# Xenium2019.net
KiCad netlist of a schematic drawn in EAGLE
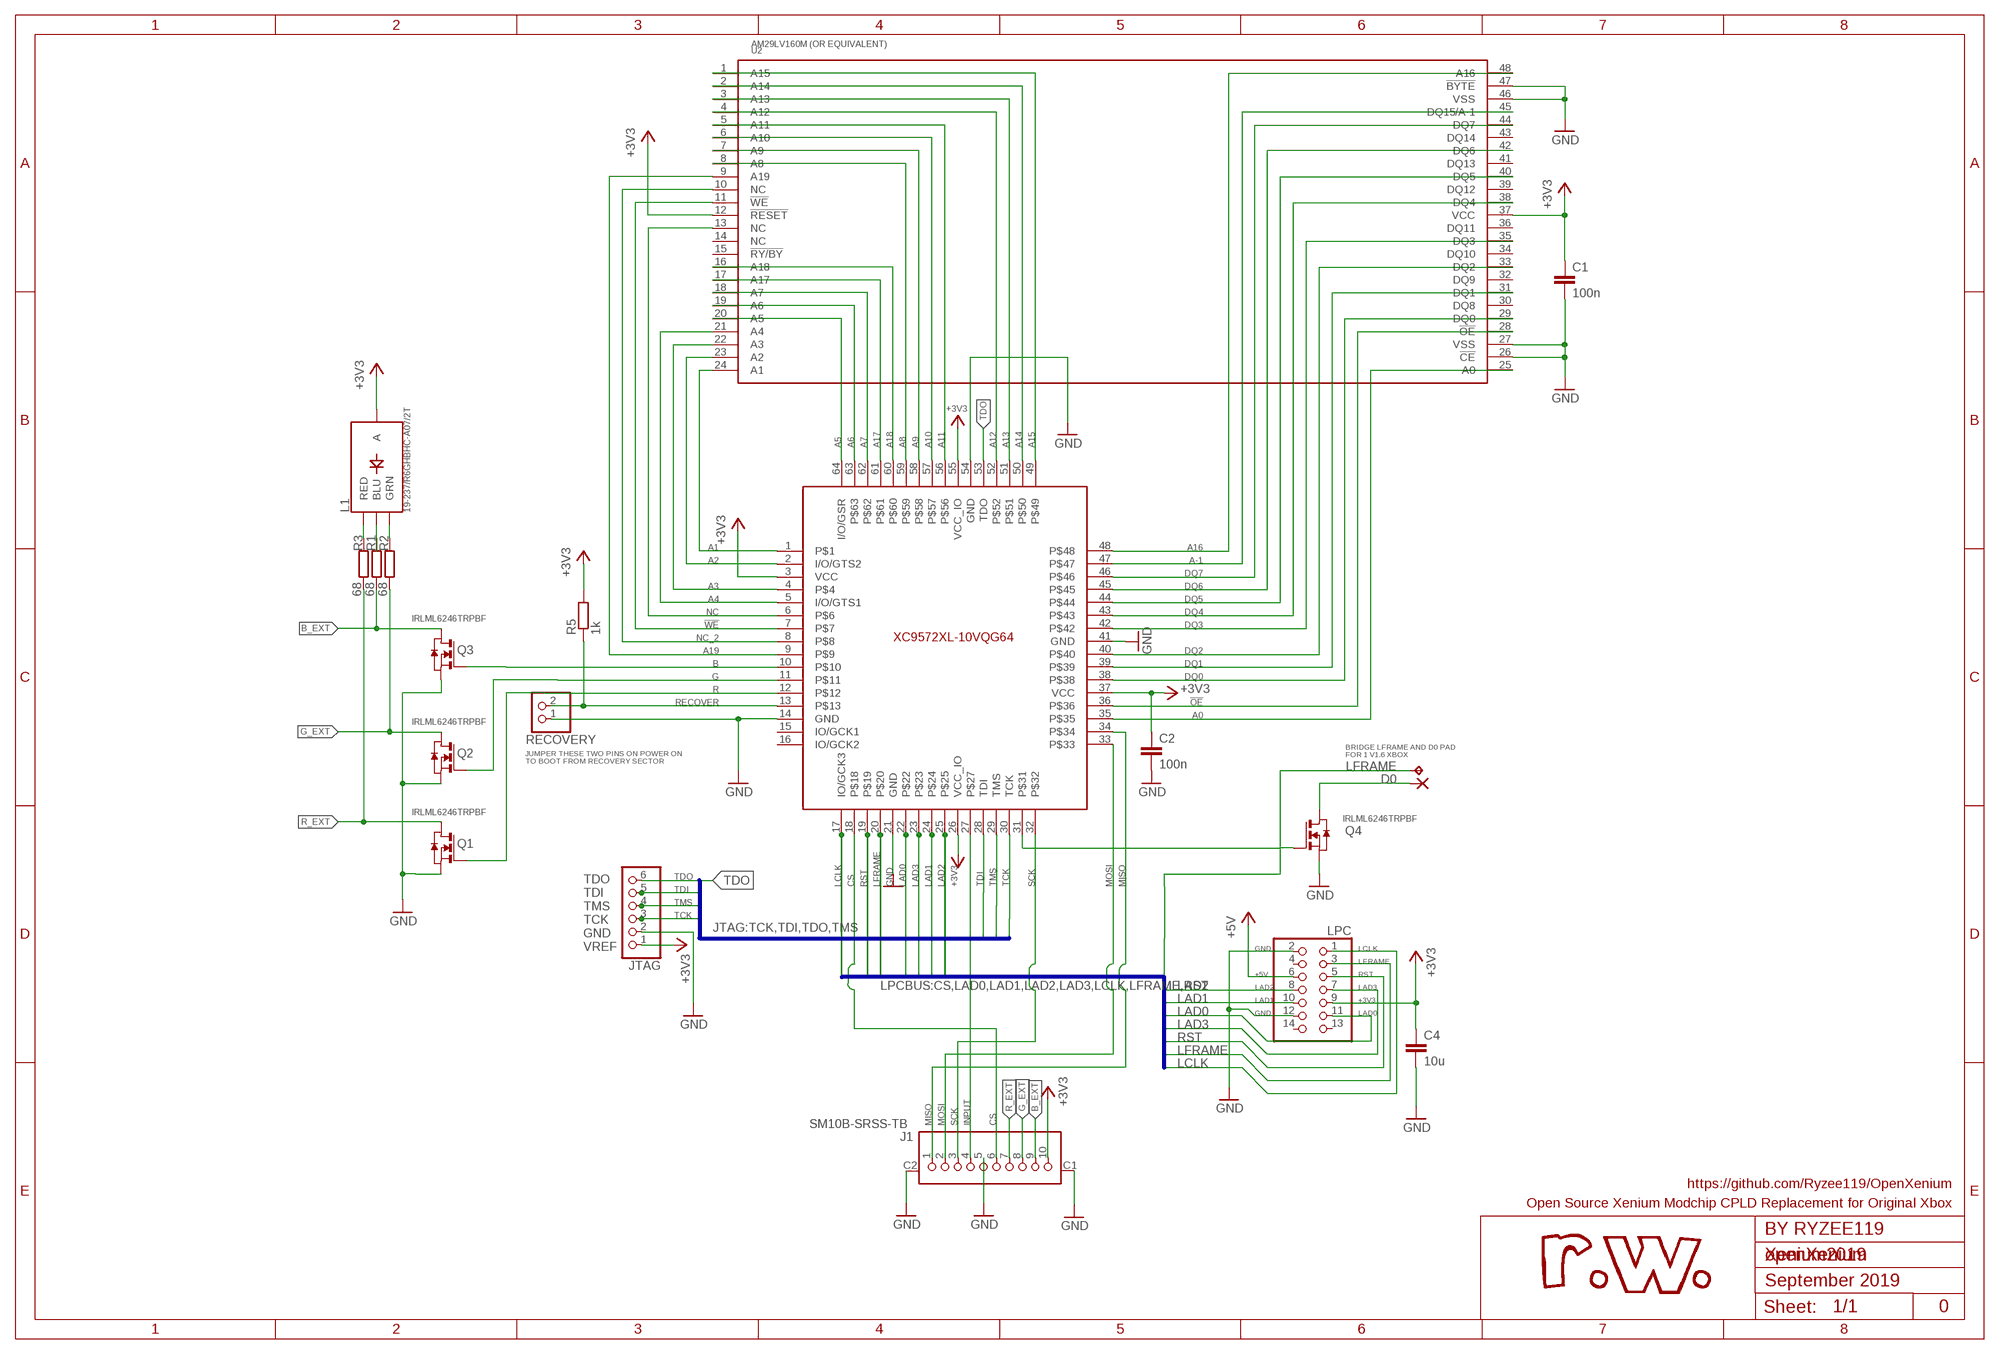
[diagram p0: schematic, sheet 1]

(export (version "E")
  (design (tool "Eeschema 10.0.6"))
  (components
    (comp (ref "C1")
      (value "100n")
      (footprint "eagle-import:C0603")
      (libsource (lib "eagle-import") (part "C-EUC0603"))
    )
    (comp (ref "C2")
      (value "100n")
      (footprint "eagle-import:C0603")
      (libsource (lib "eagle-import") (part "C-EUC0603"))
    )
    (comp (ref "C4")
      (value "10u")
      (footprint "eagle-import:C0603")
      (libsource (lib "eagle-import") (part "C-EUC0603"))
    )
    (comp (ref "D0")
      (value "SMD2")
      (footprint "eagle-import:SMD1,27-2,54")
      (libsource (lib "eagle-import") (part "SMD2"))
    )
    (comp (ref "J1")
      (value "SM10B-SRSS-TB")
      (footprint "eagle-import:SM10B-SRSS-TB")
      (libsource (lib "eagle-import") (part "SM10B-SRSS-TB"))
    )
    (comp (ref "JTAG")
      (value "PINHD-1X6")
      (footprint "eagle-import:1X06")
      (libsource (lib "eagle-import") (part "PINHD-1X6"))
    )
    (comp (ref "L1")
      (value "19-237/R6GHBHC-A07/2T")
      (footprint "eagle-import:4-SMD-R6GHBHC")
      (libsource (lib "eagle-import") (part "19-237/R6GHBHC-A07/2T"))
    )
    (comp (ref "LPC")
      (value "PINHD-2X7")
      (footprint "eagle-import:2X07")
      (libsource (lib "eagle-import") (part "PINHD-2X7"))
    )
    (comp (ref "Q1")
      (value "310mA/60V/1.6Ω")
      (footprint "eagle-import:SOT-23")
      (libsource (lib "eagle-import") (part "NMOSSOT23"))
    )
    (comp (ref "Q2")
      (value "310mA/60V/1.6Ω")
      (footprint "eagle-import:SOT-23")
      (libsource (lib "eagle-import") (part "NMOSSOT23"))
    )
    (comp (ref "Q3")
      (value "310mA/60V/1.6Ω")
      (footprint "eagle-import:SOT-23")
      (libsource (lib "eagle-import") (part "NMOSSOT23"))
    )
    (comp (ref "Q4")
      (value "310mA/60V/1.6Ω")
      (footprint "eagle-import:SOT-23")
      (libsource (lib "eagle-import") (part "NMOSSOT23"))
    )
    (comp (ref "R1")
      (value "68")
      (footprint "eagle-import:R0603")
      (libsource (lib "eagle-import") (part "R-EU_R0603"))
    )
    (comp (ref "R2")
      (value "68")
      (footprint "eagle-import:R0603")
      (libsource (lib "eagle-import") (part "R-EU_R0603"))
    )
    (comp (ref "R3")
      (value "68")
      (footprint "eagle-import:R0603")
      (libsource (lib "eagle-import") (part "R-EU_R0603"))
    )
    (comp (ref "R5")
      (value "1k")
      (footprint "eagle-import:R0603")
      (libsource (lib "eagle-import") (part "R-EU_R0603"))
    )
    (comp (ref "RECOVERY")
      (value "PINHD-1X2")
      (footprint "eagle-import:1X02")
      (libsource (lib "eagle-import") (part "PINHD-1X2"))
    )
    (comp (ref "TP1")
      (value "TPTP13SQ")
      (footprint "eagle-import:TP13SQ")
      (libsource (lib "eagle-import") (part "TPTP13SQ"))
    )
    (comp (ref "U1")
      (value "XC9572XL-10VQG64")
      (footprint "eagle-import:LQFP64")
      (libsource (lib "eagle-import") (part "XC9572XL-10VQG64"))
    )
    (comp (ref "U2")
      (value "AM29LV160M")
      (footprint "eagle-import:TSOP48")
      (libsource (lib "eagle-import") (part "AM29LV160M"))
    )
  )
  (nets
    (net (code "3") (name "+3V3") (class "Default")
      (node (ref "C1") (pin "1") (pinfunction "1_1") (pintype "passive"))
      (node (ref "C2") (pin "1") (pinfunction "1_1") (pintype "passive"))
      (node (ref "C4") (pin "1") (pinfunction "1_1") (pintype "passive"))
      (node (ref "J1") (pin "10") (pinfunction "10_10") (pintype "bidirectional"))
      (node (ref "JTAG") (pin "1") (pinfunction "1_1") (pintype "passive"))
      (node (ref "L1") (pin "P$2") (pinfunction "A_P$2") (pintype "bidirectional"))
      (node (ref "LPC") (pin "9") (pinfunction "9_9") (pintype "passive"))
      (node (ref "R5") (pin "2") (pinfunction "2_2") (pintype "passive"))
      (node (ref "U1") (pin "26") (pinfunction "VCC_IO_26") (pintype "bidirectional"))
      (node (ref "U1") (pin "3") (pinfunction "VCC_3") (pintype "bidirectional"))
      (node (ref "U1") (pin "37") (pinfunction "VCC_37") (pintype "bidirectional"))
      (node (ref "U1") (pin "55") (pinfunction "VCC_IO_55") (pintype "bidirectional"))
      (node (ref "U2") (pin "12") (pinfunction "~{RESET}_12") (pintype "bidirectional"))
      (node (ref "U2") (pin "37") (pinfunction "VCC_37") (pintype "bidirectional"))
    )
    (net (code "4") (name "+5V") (class "Default")
      (node (ref "LPC") (pin "6") (pinfunction "6_6") (pintype "passive"))
    )
    (net (code "5") (name "/A-1") (class "Default")
      (node (ref "U1") (pin "47") (pinfunction "P$47_47") (pintype "bidirectional"))
      (node (ref "U2") (pin "45") (pinfunction "DQ15/A-1_45") (pintype "bidirectional"))
    )
    (net (code "6") (name "/A0") (class "Default")
      (node (ref "U1") (pin "35") (pinfunction "P$35_35") (pintype "bidirectional"))
      (node (ref "U2") (pin "25") (pinfunction "A0_25") (pintype "bidirectional"))
    )
    (net (code "7") (name "/A1") (class "Default")
      (node (ref "U1") (pin "1") (pinfunction "P$1_1") (pintype "bidirectional"))
      (node (ref "U2") (pin "24") (pinfunction "A1_24") (pintype "bidirectional"))
    )
    (net (code "8") (name "/A2") (class "Default")
      (node (ref "U1") (pin "2") (pinfunction "I/O/GTS2_2") (pintype "bidirectional"))
      (node (ref "U2") (pin "23") (pinfunction "A2_23") (pintype "bidirectional"))
    )
    (net (code "9") (name "/A3") (class "Default")
      (node (ref "U1") (pin "4") (pinfunction "P$4_4") (pintype "bidirectional"))
      (node (ref "U2") (pin "22") (pinfunction "A3_22") (pintype "bidirectional"))
    )
    (net (code "10") (name "/A4") (class "Default")
      (node (ref "U1") (pin "5") (pinfunction "I/O/GTS1_5") (pintype "bidirectional"))
      (node (ref "U2") (pin "21") (pinfunction "A4_21") (pintype "bidirectional"))
    )
    (net (code "11") (name "/A5") (class "Default")
      (node (ref "U1") (pin "64") (pinfunction "I/O/GSR_64") (pintype "bidirectional"))
      (node (ref "U2") (pin "20") (pinfunction "A5_20") (pintype "bidirectional"))
    )
    (net (code "12") (name "/A6") (class "Default")
      (node (ref "U1") (pin "63") (pinfunction "P$63_63") (pintype "bidirectional"))
      (node (ref "U2") (pin "19") (pinfunction "A6_19") (pintype "bidirectional"))
    )
    (net (code "13") (name "/A7") (class "Default")
      (node (ref "U1") (pin "62") (pinfunction "P$62_62") (pintype "bidirectional"))
      (node (ref "U2") (pin "18") (pinfunction "A7_18") (pintype "bidirectional"))
    )
    (net (code "14") (name "/A8") (class "Default")
      (node (ref "U1") (pin "59") (pinfunction "P$59_59") (pintype "bidirectional"))
      (node (ref "U2") (pin "8") (pinfunction "A8_8") (pintype "bidirectional"))
    )
    (net (code "15") (name "/A9") (class "Default")
      (node (ref "U1") (pin "58") (pinfunction "P$58_58") (pintype "bidirectional"))
      (node (ref "U2") (pin "7") (pinfunction "A9_7") (pintype "bidirectional"))
    )
    (net (code "16") (name "/A10") (class "Default")
      (node (ref "U1") (pin "57") (pinfunction "P$57_57") (pintype "bidirectional"))
      (node (ref "U2") (pin "6") (pinfunction "A10_6") (pintype "bidirectional"))
    )
    (net (code "17") (name "/A11") (class "Default")
      (node (ref "U1") (pin "56") (pinfunction "P$56_56") (pintype "bidirectional"))
      (node (ref "U2") (pin "5") (pinfunction "A11_5") (pintype "bidirectional"))
    )
    (net (code "18") (name "/A12") (class "Default")
      (node (ref "U1") (pin "52") (pinfunction "P$52_52") (pintype "bidirectional"))
      (node (ref "U2") (pin "4") (pinfunction "A12_4") (pintype "bidirectional"))
    )
    (net (code "19") (name "/A13") (class "Default")
      (node (ref "U1") (pin "51") (pinfunction "P$51_51") (pintype "bidirectional"))
      (node (ref "U2") (pin "3") (pinfunction "A13_3") (pintype "bidirectional"))
    )
    (net (code "20") (name "/A14") (class "Default")
      (node (ref "U1") (pin "50") (pinfunction "P$50_50") (pintype "bidirectional"))
      (node (ref "U2") (pin "2") (pinfunction "A14_2") (pintype "bidirectional"))
    )
    (net (code "21") (name "/A15") (class "Default")
      (node (ref "U1") (pin "49") (pinfunction "P$49_49") (pintype "bidirectional"))
      (node (ref "U2") (pin "1") (pinfunction "A15_1") (pintype "bidirectional"))
    )
    (net (code "22") (name "/A16") (class "Default")
      (node (ref "U1") (pin "48") (pinfunction "P$48_48") (pintype "bidirectional"))
      (node (ref "U2") (pin "48") (pinfunction "A16_48") (pintype "bidirectional"))
    )
    (net (code "23") (name "/A17") (class "Default")
      (node (ref "U1") (pin "61") (pinfunction "P$61_61") (pintype "bidirectional"))
      (node (ref "U2") (pin "17") (pinfunction "A17_17") (pintype "bidirectional"))
    )
    (net (code "24") (name "/A18") (class "Default")
      (node (ref "U1") (pin "60") (pinfunction "P$60_60") (pintype "bidirectional"))
      (node (ref "U2") (pin "16") (pinfunction "A18_16") (pintype "bidirectional"))
    )
    (net (code "25") (name "/A19") (class "Default")
      (node (ref "U1") (pin "9") (pinfunction "P$9_9") (pintype "bidirectional"))
      (node (ref "U2") (pin "9") (pinfunction "A19_9") (pintype "bidirectional"))
    )
    (net (code "26") (name "/B") (class "Default")
      (node (ref "Q3") (pin "3") (pinfunction "G_3") (pintype "passive"))
      (node (ref "U1") (pin "10") (pinfunction "P$10_10") (pintype "bidirectional"))
    )
    (net (code "27") (name "/CS") (class "Default")
      (node (ref "J1") (pin "6") (pinfunction "6_6") (pintype "bidirectional"))
      (node (ref "U1") (pin "18") (pinfunction "P$18_18") (pintype "bidirectional"))
    )
    (net (code "28") (name "/DQ0") (class "Default")
      (node (ref "U1") (pin "38") (pinfunction "P$38_38") (pintype "bidirectional"))
      (node (ref "U2") (pin "29") (pinfunction "DQ0_29") (pintype "bidirectional"))
    )
    (net (code "29") (name "/DQ1") (class "Default")
      (node (ref "U1") (pin "39") (pinfunction "P$39_39") (pintype "bidirectional"))
      (node (ref "U2") (pin "31") (pinfunction "DQ1_31") (pintype "bidirectional"))
    )
    (net (code "30") (name "/DQ2") (class "Default")
      (node (ref "U1") (pin "40") (pinfunction "P$40_40") (pintype "bidirectional"))
      (node (ref "U2") (pin "33") (pinfunction "DQ2_33") (pintype "bidirectional"))
    )
    (net (code "31") (name "/DQ3") (class "Default")
      (node (ref "U1") (pin "42") (pinfunction "P$42_42") (pintype "bidirectional"))
      (node (ref "U2") (pin "35") (pinfunction "DQ3_35") (pintype "bidirectional"))
    )
    (net (code "32") (name "/DQ4") (class "Default")
      (node (ref "U1") (pin "43") (pinfunction "P$43_43") (pintype "bidirectional"))
      (node (ref "U2") (pin "38") (pinfunction "DQ4_38") (pintype "bidirectional"))
    )
    (net (code "33") (name "/DQ5") (class "Default")
      (node (ref "U1") (pin "44") (pinfunction "P$44_44") (pintype "bidirectional"))
      (node (ref "U2") (pin "40") (pinfunction "DQ5_40") (pintype "bidirectional"))
    )
    (net (code "34") (name "/DQ6") (class "Default")
      (node (ref "U1") (pin "45") (pinfunction "P$45_45") (pintype "bidirectional"))
      (node (ref "U2") (pin "42") (pinfunction "DQ6_42") (pintype "bidirectional"))
    )
    (net (code "35") (name "/DQ7") (class "Default")
      (node (ref "U1") (pin "46") (pinfunction "P$46_46") (pintype "bidirectional"))
      (node (ref "U2") (pin "44") (pinfunction "DQ7_44") (pintype "bidirectional"))
    )
    (net (code "36") (name "/G") (class "Default")
      (node (ref "Q2") (pin "3") (pinfunction "G_3") (pintype "passive"))
      (node (ref "U1") (pin "11") (pinfunction "P$11_11") (pintype "bidirectional"))
    )
    (net (code "37") (name "/INPUT") (class "Default")
      (node (ref "J1") (pin "4") (pinfunction "4_4") (pintype "bidirectional"))
      (node (ref "U1") (pin "27") (pinfunction "P$27_27") (pintype "bidirectional"))
    )
    (net (code "38") (name "/LAD0") (class "Default")
      (node (ref "LPC") (pin "11") (pinfunction "11_11") (pintype "passive"))
      (node (ref "U1") (pin "22") (pinfunction "P$22_22") (pintype "bidirectional"))
    )
    (net (code "39") (name "/LAD1") (class "Default")
      (node (ref "LPC") (pin "10") (pinfunction "10_10") (pintype "passive"))
      (node (ref "U1") (pin "24") (pinfunction "P$24_24") (pintype "bidirectional"))
    )
    (net (code "40") (name "/LAD2") (class "Default")
      (node (ref "LPC") (pin "8") (pinfunction "8_8") (pintype "passive"))
      (node (ref "U1") (pin "25") (pinfunction "P$25_25") (pintype "bidirectional"))
    )
    (net (code "41") (name "/LAD3") (class "Default")
      (node (ref "LPC") (pin "7") (pinfunction "7_7") (pintype "passive"))
      (node (ref "U1") (pin "23") (pinfunction "P$23_23") (pintype "bidirectional"))
    )
    (net (code "42") (name "/LCLK") (class "Default")
      (node (ref "LPC") (pin "1") (pinfunction "1_1") (pintype "passive"))
      (node (ref "U1") (pin "17") (pinfunction "IO/GCK3_17") (pintype "bidirectional"))
    )
    (net (code "43") (name "/LFRAME") (class "Default")
      (node (ref "LPC") (pin "3") (pinfunction "3_3") (pintype "passive"))
      (node (ref "TP1") (pin "TP") (pinfunction "TP_TP") (pintype "input"))
      (node (ref "U1") (pin "20") (pinfunction "P$20_20") (pintype "bidirectional"))
    )
    (net (code "44") (name "/MISO") (class "Default")
      (node (ref "J1") (pin "1") (pinfunction "1_1") (pintype "bidirectional"))
      (node (ref "U1") (pin "34") (pinfunction "P$34_34") (pintype "bidirectional"))
    )
    (net (code "45") (name "/MOSI") (class "Default")
      (node (ref "J1") (pin "2") (pinfunction "2_2") (pintype "bidirectional"))
      (node (ref "U1") (pin "33") (pinfunction "P$33_33") (pintype "bidirectional"))
    )
    (net (code "46") (name "/NC") (class "Default")
      (node (ref "U1") (pin "6") (pinfunction "P$6_6") (pintype "bidirectional"))
      (node (ref "U2") (pin "13") (pinfunction "NC_13") (pintype "bidirectional"))
    )
    (net (code "47") (name "/NC_2") (class "Default")
      (node (ref "U1") (pin "8") (pinfunction "P$8_8") (pintype "bidirectional"))
      (node (ref "U2") (pin "10") (pinfunction "NC_10") (pintype "bidirectional"))
    )
    (net (code "48") (name "/R") (class "Default")
      (node (ref "Q1") (pin "3") (pinfunction "G_3") (pintype "passive"))
      (node (ref "U1") (pin "12") (pinfunction "P$12_12") (pintype "bidirectional"))
    )
    (net (code "49") (name "/RECOVER") (class "Default")
      (node (ref "R5") (pin "1") (pinfunction "1_1") (pintype "passive"))
      (node (ref "RECOVERY") (pin "2") (pinfunction "2_2") (pintype "passive"))
      (node (ref "U1") (pin "13") (pinfunction "P$13_13") (pintype "bidirectional"))
    )
    (net (code "50") (name "/RST") (class "Default")
      (node (ref "LPC") (pin "5") (pinfunction "5_5") (pintype "passive"))
      (node (ref "U1") (pin "19") (pinfunction "P$19_19") (pintype "bidirectional"))
    )
    (net (code "51") (name "/SCK") (class "Default")
      (node (ref "J1") (pin "3") (pinfunction "3_3") (pintype "bidirectional"))
      (node (ref "U1") (pin "32") (pinfunction "P$32_32") (pintype "bidirectional"))
    )
    (net (code "52") (name "/TCK") (class "Default")
      (node (ref "JTAG") (pin "3") (pinfunction "3_3") (pintype "passive"))
      (node (ref "U1") (pin "30") (pinfunction "TCK_30") (pintype "bidirectional"))
    )
    (net (code "53") (name "/TDI") (class "Default")
      (node (ref "JTAG") (pin "5") (pinfunction "5_5") (pintype "passive"))
      (node (ref "U1") (pin "28") (pinfunction "TDI_28") (pintype "bidirectional"))
    )
    (net (code "54") (name "/TMS") (class "Default")
      (node (ref "JTAG") (pin "4") (pinfunction "4_4") (pintype "passive"))
      (node (ref "U1") (pin "29") (pinfunction "TMS_29") (pintype "bidirectional"))
    )
    (net (code "57") (name "/~{OE}") (class "Default")
      (node (ref "U1") (pin "36") (pinfunction "P$36_36") (pintype "bidirectional"))
      (node (ref "U2") (pin "28") (pinfunction "~{OE}_28") (pintype "bidirectional"))
    )
    (net (code "58") (name "/~{WE}") (class "Default")
      (node (ref "U1") (pin "7") (pinfunction "P$7_7") (pintype "bidirectional"))
      (node (ref "U2") (pin "11") (pinfunction "~{WE}_11") (pintype "bidirectional"))
    )
    (net (code "59") (name "B_EXT") (class "Default")
      (node (ref "J1") (pin "9") (pinfunction "9_9") (pintype "bidirectional"))
      (node (ref "Q3") (pin "1") (pinfunction "D_1") (pintype "passive"))
      (node (ref "R1") (pin "2") (pinfunction "2_2") (pintype "passive"))
    )
    (net (code "60") (name "GND") (class "Default")
      (node (ref "C1") (pin "2") (pinfunction "2_2") (pintype "passive"))
      (node (ref "C2") (pin "2") (pinfunction "2_2") (pintype "passive"))
      (node (ref "C4") (pin "2") (pinfunction "2_2") (pintype "passive"))
      (node (ref "J1") (pin "5") (pinfunction "5_5") (pintype "bidirectional"))
      (node (ref "J1") (pin "C1") (pinfunction "MNT2_C1") (pintype "bidirectional"))
      (node (ref "J1") (pin "C2") (pinfunction "MNT1_C2") (pintype "bidirectional"))
      (node (ref "JTAG") (pin "2") (pinfunction "2_2") (pintype "passive"))
      (node (ref "LPC") (pin "12") (pinfunction "12_12") (pintype "passive"))
      (node (ref "LPC") (pin "2") (pinfunction "2_2") (pintype "passive"))
      (node (ref "Q1") (pin "2") (pinfunction "S_2") (pintype "passive"))
      (node (ref "Q2") (pin "2") (pinfunction "S_2") (pintype "passive"))
      (node (ref "Q3") (pin "2") (pinfunction "S_2") (pintype "passive"))
      (node (ref "Q4") (pin "2") (pinfunction "S_2") (pintype "passive"))
      (node (ref "RECOVERY") (pin "1") (pinfunction "1_1") (pintype "passive"))
      (node (ref "U1") (pin "14") (pinfunction "GND_14") (pintype "bidirectional"))
      (node (ref "U1") (pin "21") (pinfunction "GND_21") (pintype "bidirectional"))
      (node (ref "U1") (pin "41") (pinfunction "GND_41") (pintype "bidirectional"))
      (node (ref "U1") (pin "54") (pinfunction "GND_54") (pintype "bidirectional"))
      (node (ref "U2") (pin "26") (pinfunction "~{CE}_26") (pintype "bidirectional"))
      (node (ref "U2") (pin "27") (pinfunction "VSS_27") (pintype "bidirectional"))
      (node (ref "U2") (pin "46") (pinfunction "VSS_46") (pintype "bidirectional"))
      (node (ref "U2") (pin "47") (pinfunction "~{BYTE}_47") (pintype "bidirectional"))
    )
    (net (code "61") (name "G_EXT") (class "Default")
      (node (ref "J1") (pin "8") (pinfunction "8_8") (pintype "bidirectional"))
      (node (ref "Q2") (pin "1") (pinfunction "D_1") (pintype "passive"))
      (node (ref "R2") (pin "2") (pinfunction "2_2") (pintype "passive"))
    )
    (net (code "62") (name "Net-(D0-P)") (class "Default")
      (node (ref "D0") (pin "1") (pinfunction "P_1") (pintype "passive"))
      (node (ref "Q4") (pin "1") (pinfunction "D_1") (pintype "passive"))
    )
    (net (code "63") (name "Net-(L1-BLU)") (class "Default")
      (node (ref "L1") (pin "P$4") (pinfunction "BLU_P$4") (pintype "bidirectional"))
      (node (ref "R1") (pin "1") (pinfunction "1_1") (pintype "passive"))
    )
    (net (code "64") (name "Net-(L1-GRN)") (class "Default")
      (node (ref "L1") (pin "P$3") (pinfunction "GRN_P$3") (pintype "bidirectional"))
      (node (ref "R2") (pin "1") (pinfunction "1_1") (pintype "passive"))
    )
    (net (code "65") (name "Net-(L1-RED)") (class "Default")
      (node (ref "L1") (pin "P$1") (pinfunction "RED_P$1") (pintype "bidirectional"))
      (node (ref "R3") (pin "1") (pinfunction "1_1") (pintype "passive"))
    )
    (net (code "66") (name "Net-(Q4-G)") (class "Default")
      (node (ref "Q4") (pin "3") (pinfunction "G_3") (pintype "passive"))
      (node (ref "U1") (pin "31") (pinfunction "P$31_31") (pintype "bidirectional"))
    )
    (net (code "67") (name "R_EXT") (class "Default")
      (node (ref "J1") (pin "7") (pinfunction "7_7") (pintype "bidirectional"))
      (node (ref "Q1") (pin "1") (pinfunction "D_1") (pintype "passive"))
      (node (ref "R3") (pin "2") (pinfunction "2_2") (pintype "passive"))
    )
    (net (code "68") (name "TDO") (class "Default")
      (node (ref "JTAG") (pin "6") (pinfunction "6_6") (pintype "passive"))
      (node (ref "U1") (pin "53") (pinfunction "TDO_53") (pintype "bidirectional"))
    )
    (net (code "69") (name "unconnected-(LPC-Pad4)") (class "Default")
      (node (ref "LPC") (pin "4") (pinfunction "4_4") (pintype "passive"))
    )
    (net (code "70") (name "unconnected-(LPC-Pad13)") (class "Default")
      (node (ref "LPC") (pin "13") (pinfunction "13_13") (pintype "passive"))
    )
    (net (code "71") (name "unconnected-(LPC-Pad14)") (class "Default")
      (node (ref "LPC") (pin "14") (pinfunction "14_14") (pintype "passive"))
    )
    (net (code "72") (name "unconnected-(U1-IO{slash}GCK1-Pad15)") (class "Default")
      (node (ref "U1") (pin "15") (pinfunction "IO/GCK1_15") (pintype "bidirectional"))
    )
    (net (code "73") (name "unconnected-(U1-IO{slash}GCK2-Pad16)") (class "Default")
      (node (ref "U1") (pin "16") (pinfunction "IO/GCK2_16") (pintype "bidirectional"))
    )
    (net (code "74") (name "unconnected-(U2-DQ8-Pad30)") (class "Default")
      (node (ref "U2") (pin "30") (pinfunction "DQ8_30") (pintype "bidirectional"))
    )
    (net (code "75") (name "unconnected-(U2-DQ9-Pad32)") (class "Default")
      (node (ref "U2") (pin "32") (pinfunction "DQ9_32") (pintype "bidirectional"))
    )
    (net (code "76") (name "unconnected-(U2-DQ10-Pad34)") (class "Default")
      (node (ref "U2") (pin "34") (pinfunction "DQ10_34") (pintype "bidirectional"))
    )
    (net (code "77") (name "unconnected-(U2-DQ11-Pad36)") (class "Default")
      (node (ref "U2") (pin "36") (pinfunction "DQ11_36") (pintype "bidirectional"))
    )
    (net (code "78") (name "unconnected-(U2-DQ12-Pad39)") (class "Default")
      (node (ref "U2") (pin "39") (pinfunction "DQ12_39") (pintype "bidirectional"))
    )
    (net (code "79") (name "unconnected-(U2-DQ13-Pad41)") (class "Default")
      (node (ref "U2") (pin "41") (pinfunction "DQ13_41") (pintype "bidirectional"))
    )
    (net (code "80") (name "unconnected-(U2-DQ14-Pad43)") (class "Default")
      (node (ref "U2") (pin "43") (pinfunction "DQ14_43") (pintype "bidirectional"))
    )
    (net (code "81") (name "unconnected-(U2-NC-Pad14)") (class "Default")
      (node (ref "U2") (pin "14") (pinfunction "NC_14") (pintype "bidirectional"))
    )
    (net (code "82") (name "unconnected-(U2-~{RY{slash}BY}-Pad15)") (class "Default")
      (node (ref "U2") (pin "15") (pinfunction "~{RY/BY}_15") (pintype "bidirectional"))
    )
  )
)
